# finalboard.net
KiCad netlist of a schematic drawn in EAGLE
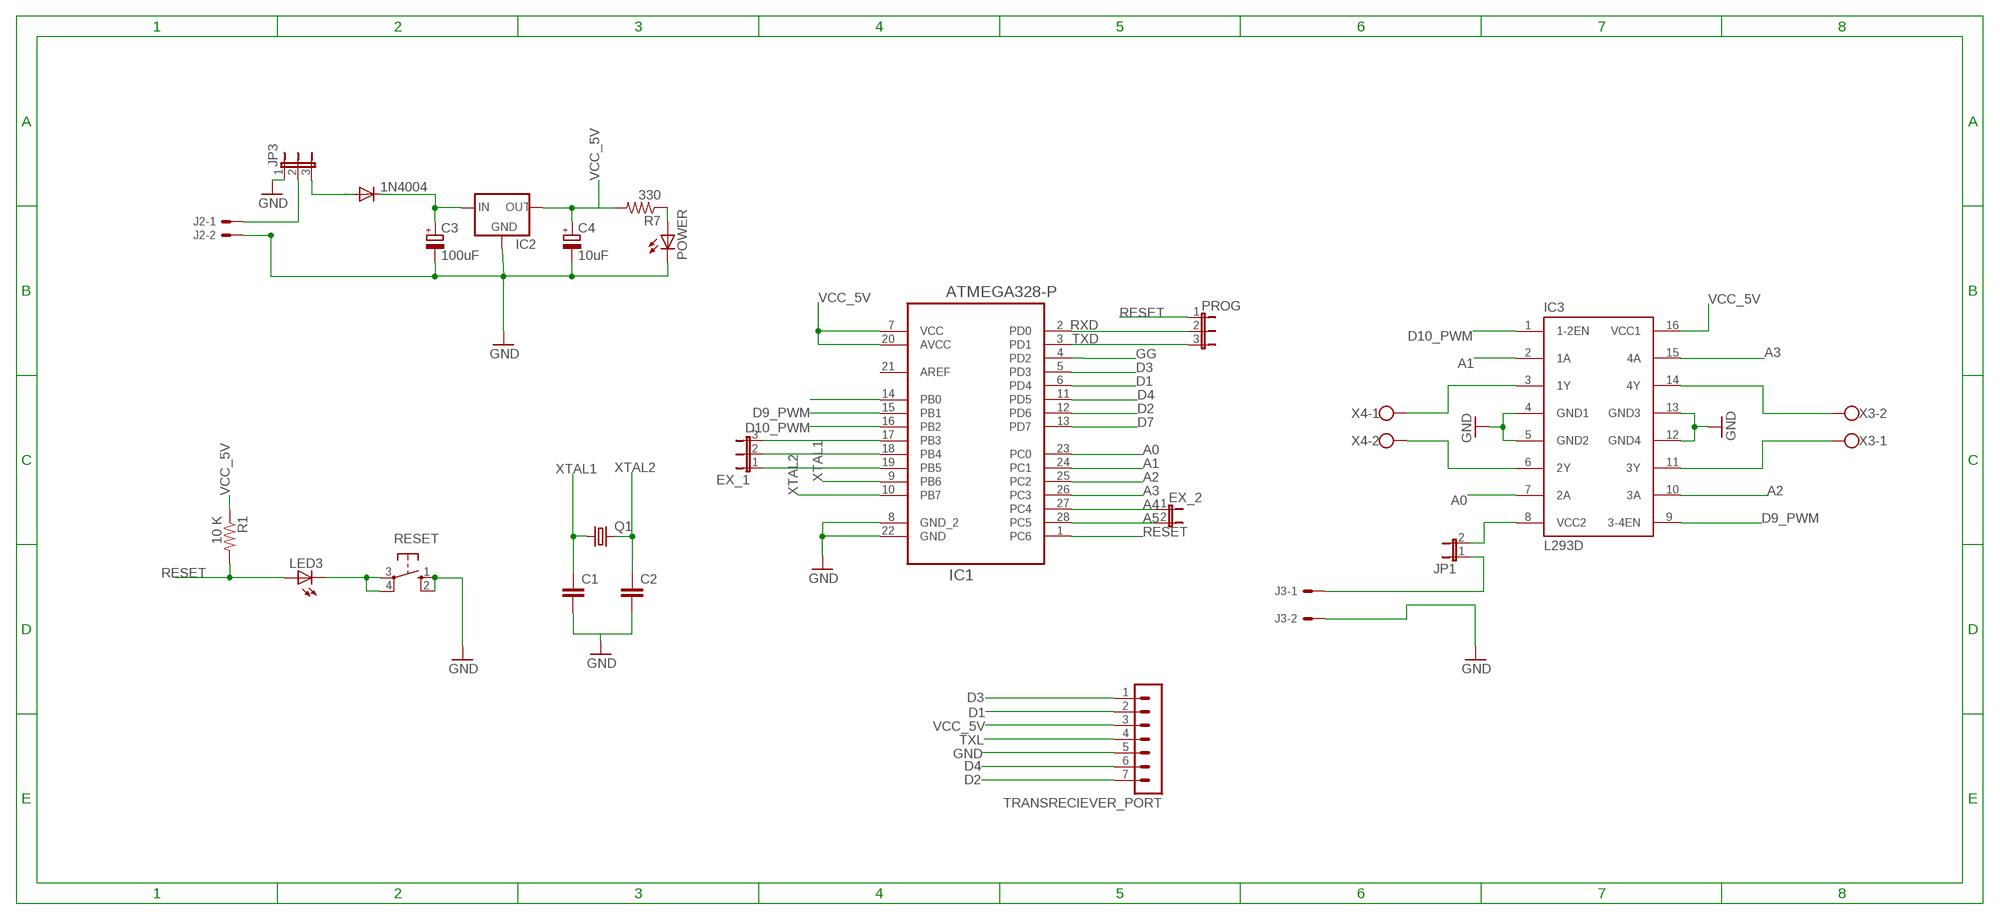
[diagram p0: schematic, sheet 1]

(export (version "E")
  (design (tool "Eeschema 10.0.6"))
  (components
    (comp (ref "1N4004")
      (value "1N4004")
      (footprint "eagle-import:DO41-10")
      (libsource (lib "eagle-import") (part "1N4004"))
    )
    (comp (ref "ATMEGA328-P")
      (value "IC1")
      (footprint "eagle-import:DIP254P762X457-28")
      (fields (field (name "MPN") "ATMEGA328P-PU"))
      (libsource (lib "eagle-import") (part "ATMEGA328P-PU"))
    )
    (comp (ref "C1")
      (value "C-EU025-025X050")
      (footprint "eagle-import:C025-025X050")
      (libsource (lib "eagle-import") (part "C-EU025-025X050"))
    )
    (comp (ref "C2")
      (value "C-EU025-025X050")
      (footprint "eagle-import:C025-025X050")
      (libsource (lib "eagle-import") (part "C-EU025-025X050"))
    )
    (comp (ref "C3")
      (value "100uF")
      (footprint "eagle-import:E2,5-6E")
      (libsource (lib "eagle-import") (part "CPOL-EUE2,5-6E"))
    )
    (comp (ref "C4")
      (value "10uF")
      (footprint "eagle-import:E2-5")
      (libsource (lib "eagle-import") (part "CPOL-EUE2-5"))
    )
    (comp (ref "EX_1")
      (value "JP2E")
      (footprint "eagle-import:JP2")
      (libsource (lib "eagle-import") (part "JP2E"))
    )
    (comp (ref "EX_2")
      (value "JP1E")
      (footprint "eagle-import:JP1")
      (libsource (lib "eagle-import") (part "JP1E"))
    )
    (comp (ref "IC2")
      (value "78XXL")
      (footprint "eagle-import:78XXL")
      (libsource (lib "eagle-import") (part "78XXL"))
    )
    (comp (ref "IC3")
      (value "L293D")
      (footprint "eagle-import:DIL16")
      (libsource (lib "eagle-import") (part "L293D"))
    )
    (comp (ref "J2")
      (value "22-05-7028-02")
      (footprint "eagle-import:7395-02")
      (libsource (lib "eagle-import") (part "22-?-0205-7028"))
    )
    (comp (ref "J3")
      (value "22-05-7028-02")
      (footprint "eagle-import:7395-02")
      (libsource (lib "eagle-import") (part "22-?-0205-7028"))
    )
    (comp (ref "JP1")
      (value "JP1E")
      (footprint "eagle-import:JP1")
      (libsource (lib "eagle-import") (part "JP1E"))
    )
    (comp (ref "JP3")
      (value "JP2E")
      (footprint "eagle-import:JP2")
      (libsource (lib "eagle-import") (part "JP2E"))
    )
    (comp (ref "LED3")
      (value "LED3MM")
      (footprint "eagle-import:LED3MM")
      (libsource (lib "eagle-import") (part "LED3MM"))
    )
    (comp (ref "POWER")
      (value "LED3MM")
      (footprint "eagle-import:LED3MM")
      (libsource (lib "eagle-import") (part "LED3MM"))
    )
    (comp (ref "PROG")
      (value "JP2E")
      (footprint "eagle-import:JP2")
      (libsource (lib "eagle-import") (part "JP2E"))
    )
    (comp (ref "Q1")
      (value "CRYSTALHC49U70")
      (footprint "eagle-import:HC49U70")
      (libsource (lib "eagle-import") (part "CRYSTALHC49U70"))
    )
    (comp (ref "R1")
      (value "10 K")
      (footprint "eagle-import:0207_12")
      (libsource (lib "eagle-import") (part "R-US_0207/12"))
    )
    (comp (ref "R7")
      (value "330")
      (footprint "eagle-import:0204_7")
      (libsource (lib "eagle-import") (part "R-US_0204/7"))
    )
    (comp (ref "RESET")
      (value "10-XX")
      (footprint "eagle-import:B3F-10XX")
      (fields (field (name "MPN") "B3F-1000"))
      (libsource (lib "eagle-import") (part "10-XX"))
    )
    (comp (ref "TRANSRECIEVER_PORT")
      (value "MA07-1")
      (footprint "eagle-import:MA07-1")
      (libsource (lib "eagle-import") (part "MA07-1"))
    )
    (comp (ref "X3")
      (value "W237-102")
      (footprint "eagle-import:W237-102")
      (fields (field (name "MPN") "237-102"))
      (libsource (lib "eagle-import") (part "W237-102"))
    )
    (comp (ref "X4")
      (value "W237-102")
      (footprint "eagle-import:W237-102")
      (fields (field (name "MPN") "237-102"))
      (libsource (lib "eagle-import") (part "W237-102"))
    )
  )
  (nets
    (net (code "1") (name "/A0") (class "Default")
      (node (ref "ATMEGA328-P") (pin "23") (pinfunction "PC0_23") (pintype "bidirectional"))
      (node (ref "IC3") (pin "7") (pinfunction "2A_7") (pintype "input"))
    )
    (net (code "2") (name "/A1") (class "Default")
      (node (ref "ATMEGA328-P") (pin "24") (pinfunction "PC1_24") (pintype "bidirectional"))
      (node (ref "IC3") (pin "2") (pinfunction "1A_2") (pintype "input"))
    )
    (net (code "3") (name "/A2") (class "Default")
      (node (ref "ATMEGA328-P") (pin "25") (pinfunction "PC2_25") (pintype "bidirectional"))
      (node (ref "IC3") (pin "10") (pinfunction "3A_10") (pintype "input"))
    )
    (net (code "4") (name "/A3") (class "Default")
      (node (ref "ATMEGA328-P") (pin "26") (pinfunction "PC3_26") (pintype "bidirectional"))
      (node (ref "IC3") (pin "15") (pinfunction "4A_15") (pintype "input"))
    )
    (net (code "5") (name "/A4") (class "Default")
      (node (ref "ATMEGA328-P") (pin "27") (pinfunction "PC4_27") (pintype "bidirectional"))
      (node (ref "EX_2") (pin "1") (pinfunction "1_1") (pintype "passive"))
    )
    (net (code "6") (name "/A5") (class "Default")
      (node (ref "ATMEGA328-P") (pin "28") (pinfunction "PC5_28") (pintype "bidirectional"))
      (node (ref "EX_2") (pin "2") (pinfunction "2_2") (pintype "passive"))
    )
    (net (code "7") (name "/D1") (class "Default")
      (node (ref "ATMEGA328-P") (pin "6") (pinfunction "PD4_6") (pintype "bidirectional"))
      (node (ref "TRANSRECIEVER_PORT") (pin "2") (pinfunction "2_2") (pintype "passive"))
    )
    (net (code "8") (name "/D2") (class "Default")
      (node (ref "ATMEGA328-P") (pin "12") (pinfunction "PD6_12") (pintype "bidirectional"))
      (node (ref "TRANSRECIEVER_PORT") (pin "7") (pinfunction "7_7") (pintype "passive"))
    )
    (net (code "9") (name "/D3") (class "Default")
      (node (ref "ATMEGA328-P") (pin "5") (pinfunction "PD3_5") (pintype "bidirectional"))
      (node (ref "TRANSRECIEVER_PORT") (pin "1") (pinfunction "1_1") (pintype "passive"))
    )
    (net (code "10") (name "/D4") (class "Default")
      (node (ref "ATMEGA328-P") (pin "11") (pinfunction "PD5_11") (pintype "bidirectional"))
      (node (ref "TRANSRECIEVER_PORT") (pin "6") (pinfunction "6_6") (pintype "passive"))
    )
    (net (code "11") (name "/D7") (class "Default")
      (node (ref "ATMEGA328-P") (pin "13") (pinfunction "PD7_13") (pintype "bidirectional"))
    )
    (net (code "12") (name "/D9_PWM") (class "Default")
      (node (ref "ATMEGA328-P") (pin "15") (pinfunction "PB1_15") (pintype "bidirectional"))
      (node (ref "IC3") (pin "9") (pinfunction "3-4EN_9") (pintype "input"))
    )
    (net (code "13") (name "/D10_PWM") (class "Default")
      (node (ref "ATMEGA328-P") (pin "16") (pinfunction "PB2_16") (pintype "bidirectional"))
      (node (ref "IC3") (pin "1") (pinfunction "1-2EN_1") (pintype "input"))
    )
    (net (code "14") (name "/GG") (class "Default")
      (node (ref "ATMEGA328-P") (pin "4") (pinfunction "PD2_4") (pintype "bidirectional"))
    )
    (net (code "15") (name "/RESET") (class "Default")
      (node (ref "ATMEGA328-P") (pin "1") (pinfunction "PC6_1") (pintype "bidirectional"))
      (node (ref "LED3") (pin "A") (pinfunction "A_A") (pintype "passive"))
      (node (ref "PROG") (pin "1") (pinfunction "1_1") (pintype "passive"))
      (node (ref "R1") (pin "2") (pinfunction "2_2") (pintype "passive"))
    )
    (net (code "16") (name "/RXD") (class "Default")
      (node (ref "ATMEGA328-P") (pin "2") (pinfunction "PD0_2") (pintype "bidirectional"))
      (node (ref "PROG") (pin "2") (pinfunction "2_2") (pintype "passive"))
    )
    (net (code "17") (name "/TXD") (class "Default")
      (node (ref "ATMEGA328-P") (pin "3") (pinfunction "PD1_3") (pintype "bidirectional"))
      (node (ref "PROG") (pin "3") (pinfunction "3_3") (pintype "passive"))
    )
    (net (code "18") (name "/TXL") (class "Default")
      (node (ref "ATMEGA328-P") (pin "14") (pinfunction "PB0_14") (pintype "bidirectional"))
      (node (ref "TRANSRECIEVER_PORT") (pin "4") (pinfunction "4_4") (pintype "passive"))
    )
    (net (code "19") (name "/VCC_5V") (class "Default")
      (node (ref "ATMEGA328-P") (pin "20") (pinfunction "AVCC_20") (pintype "power_in"))
      (node (ref "ATMEGA328-P") (pin "7") (pinfunction "VCC_7") (pintype "power_in"))
      (node (ref "C4") (pin "+") (pinfunction "+_+") (pintype "passive"))
      (node (ref "IC2") (pin "OUT") (pinfunction "OUT_OUT") (pintype "passive"))
      (node (ref "IC3") (pin "16") (pinfunction "VCC1_16") (pintype "power_in"))
      (node (ref "R1") (pin "1") (pinfunction "1_1") (pintype "passive"))
      (node (ref "R7") (pin "2") (pinfunction "2_2") (pintype "passive"))
      (node (ref "TRANSRECIEVER_PORT") (pin "3") (pinfunction "3_3") (pintype "passive"))
    )
    (net (code "20") (name "/XTAL1") (class "Default")
      (node (ref "ATMEGA328-P") (pin "9") (pinfunction "PB6_9") (pintype "bidirectional"))
      (node (ref "C1") (pin "1") (pinfunction "1_1") (pintype "passive"))
      (node (ref "Q1") (pin "1") (pinfunction "1_1") (pintype "passive"))
    )
    (net (code "21") (name "/XTAL2") (class "Default")
      (node (ref "ATMEGA328-P") (pin "10") (pinfunction "PB7_10") (pintype "bidirectional"))
      (node (ref "C2") (pin "1") (pinfunction "1_1") (pintype "passive"))
      (node (ref "Q1") (pin "2") (pinfunction "2_2") (pintype "passive"))
    )
    (net (code "22") (name "GND") (class "Default")
      (node (ref "ATMEGA328-P") (pin "22") (pinfunction "GND_22") (pintype "passive"))
      (node (ref "ATMEGA328-P") (pin "8") (pinfunction "GND_2_8") (pintype "passive"))
      (node (ref "C1") (pin "2") (pinfunction "2_2") (pintype "passive"))
      (node (ref "C2") (pin "2") (pinfunction "2_2") (pintype "passive"))
      (node (ref "C3") (pin "-") (pinfunction "-_-") (pintype "passive"))
      (node (ref "C4") (pin "-") (pinfunction "-_-") (pintype "passive"))
      (node (ref "IC2") (pin "GND") (pinfunction "GND_GND") (pintype "input"))
      (node (ref "IC3") (pin "12") (pinfunction "GND4_12") (pintype "power_in"))
      (node (ref "IC3") (pin "13") (pinfunction "GND3_13") (pintype "power_in"))
      (node (ref "IC3") (pin "4") (pinfunction "GND1_4") (pintype "power_in"))
      (node (ref "IC3") (pin "5") (pinfunction "GND2_5") (pintype "power_in"))
      (node (ref "J2") (pin "2") (pinfunction "S_2") (pintype "passive"))
      (node (ref "J3") (pin "2") (pinfunction "S_2") (pintype "passive"))
      (node (ref "JP3") (pin "1") (pinfunction "1_1") (pintype "passive"))
      (node (ref "POWER") (pin "K") (pinfunction "C_K") (pintype "passive"))
      (node (ref "RESET") (pin "1") (pinfunction "S_1") (pintype "passive"))
      (node (ref "RESET") (pin "2") (pinfunction "S1_2") (pintype "passive"))
      (node (ref "TRANSRECIEVER_PORT") (pin "5") (pinfunction "5_5") (pintype "passive"))
    )
    (net (code "23") (name "Net-(1N4004-PadA)") (class "Default")
      (node (ref "1N4004") (pin "A") (pinfunction "A_A") (pintype "passive"))
      (node (ref "JP3") (pin "3") (pinfunction "3_3") (pintype "passive"))
    )
    (net (code "24") (name "Net-(1N4004-PadC)") (class "Default")
      (node (ref "1N4004") (pin "C") (pinfunction "C_C") (pintype "passive"))
      (node (ref "C3") (pin "+") (pinfunction "+_+") (pintype "passive"))
      (node (ref "IC2") (pin "IN") (pinfunction "IN_IN") (pintype "input"))
    )
    (net (code "25") (name "Net-(ATMEGA328-P-PB3)") (class "Default")
      (node (ref "ATMEGA328-P") (pin "17") (pinfunction "PB3_17") (pintype "bidirectional"))
      (node (ref "EX_1") (pin "3") (pinfunction "3_3") (pintype "passive"))
    )
    (net (code "26") (name "Net-(ATMEGA328-P-PB4)") (class "Default")
      (node (ref "ATMEGA328-P") (pin "18") (pinfunction "PB4_18") (pintype "bidirectional"))
      (node (ref "EX_1") (pin "2") (pinfunction "2_2") (pintype "passive"))
    )
    (net (code "27") (name "Net-(ATMEGA328-P-PB5)") (class "Default")
      (node (ref "ATMEGA328-P") (pin "19") (pinfunction "PB5_19") (pintype "bidirectional"))
      (node (ref "EX_1") (pin "1") (pinfunction "1_1") (pintype "passive"))
    )
    (net (code "28") (name "Net-(IC3-1Y)") (class "Default")
      (node (ref "IC3") (pin "3") (pinfunction "1Y_3") (pintype "output"))
      (node (ref "X4") (pin "1") (pinfunction "KL_1") (pintype "passive"))
    )
    (net (code "29") (name "Net-(IC3-2Y)") (class "Default")
      (node (ref "IC3") (pin "6") (pinfunction "2Y_6") (pintype "output"))
      (node (ref "X4") (pin "2") (pinfunction "KL_2") (pintype "passive"))
    )
    (net (code "30") (name "Net-(IC3-3Y)") (class "Default")
      (node (ref "IC3") (pin "11") (pinfunction "3Y_11") (pintype "output"))
      (node (ref "X3") (pin "1") (pinfunction "KL_1") (pintype "passive"))
    )
    (net (code "31") (name "Net-(IC3-4Y)") (class "Default")
      (node (ref "IC3") (pin "14") (pinfunction "4Y_14") (pintype "output"))
      (node (ref "X3") (pin "2") (pinfunction "KL_2") (pintype "passive"))
    )
    (net (code "32") (name "Net-(IC3-VCC2)") (class "Default")
      (node (ref "IC3") (pin "8") (pinfunction "VCC2_8") (pintype "power_in"))
      (node (ref "JP1") (pin "2") (pinfunction "2_2") (pintype "passive"))
    )
    (net (code "33") (name "Net-(J2A-S)") (class "Default")
      (node (ref "J2") (pin "1") (pinfunction "S_1") (pintype "passive"))
      (node (ref "JP3") (pin "2") (pinfunction "2_2") (pintype "passive"))
    )
    (net (code "34") (name "Net-(J3A-S)") (class "Default")
      (node (ref "J3") (pin "1") (pinfunction "S_1") (pintype "passive"))
      (node (ref "JP1") (pin "1") (pinfunction "1_1") (pintype "passive"))
    )
    (net (code "35") (name "Net-(LED3-C)") (class "Default")
      (node (ref "LED3") (pin "K") (pinfunction "C_K") (pintype "passive"))
      (node (ref "RESET") (pin "3") (pinfunction "P_3") (pintype "passive"))
      (node (ref "RESET") (pin "4") (pinfunction "P1_4") (pintype "passive"))
    )
    (net (code "36") (name "Net-(POWER-PadA)") (class "Default")
      (node (ref "POWER") (pin "A") (pinfunction "A_A") (pintype "passive"))
      (node (ref "R7") (pin "1") (pinfunction "1_1") (pintype "passive"))
    )
    (net (code "37") (name "unconnected-(ATMEGA328-P-AREF-Pad21)") (class "Default")
      (node (ref "ATMEGA328-P") (pin "21") (pinfunction "AREF_21") (pintype "input"))
    )
  )
)
